# sensor-board.net
KiCad netlist of a schematic drawn in EAGLE
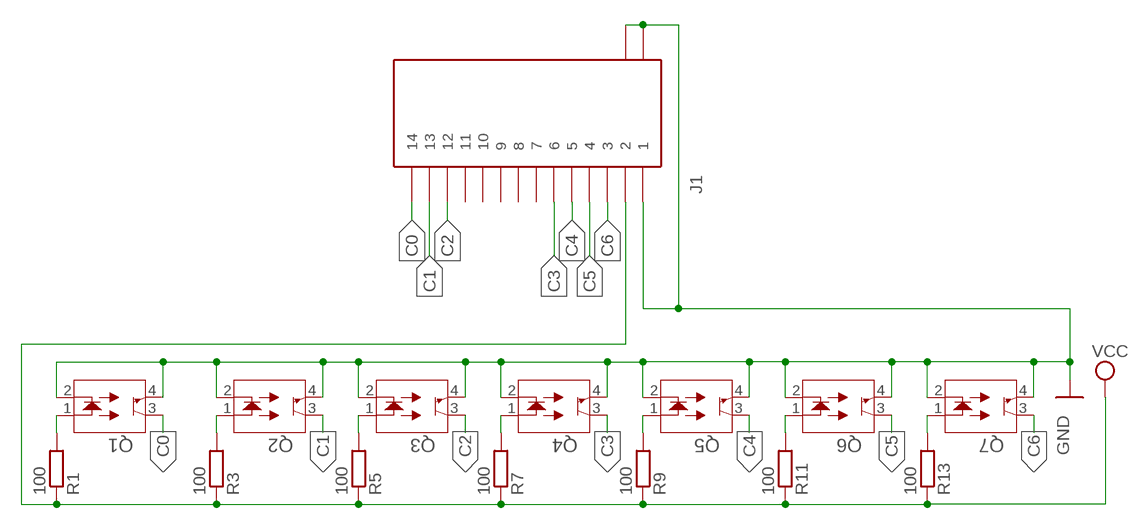
[diagram p0: schematic, sheet 1]

(export (version "E")
  (design (tool "Eeschema 10.0.6"))
  (components
    (comp (ref "J1")
      (value "686114148922")
      (footprint "eagle-import:686114148922")
      (fields (field (name "MOUSER_PART_NUMBER") "710-686114148922"))
      (libsource (lib "eagle-import") (part "686114148922"))
    )
    (comp (ref "Q1")
      (value "QRE1113")
      (footprint "eagle-import:DIP4_100AQ_ONS")
      (fields (field (name "COPYRIGHT") "Copyright (C) 2024 Ultra Librarian. All rights reserved."))
      (libsource (lib "eagle-import") (part "QRE1113"))
    )
    (comp (ref "Q2")
      (value "QRE1113")
      (footprint "eagle-import:DIP4_100AQ_ONS")
      (fields (field (name "COPYRIGHT") "Copyright (C) 2024 Ultra Librarian. All rights reserved."))
      (libsource (lib "eagle-import") (part "QRE1113"))
    )
    (comp (ref "Q3")
      (value "QRE1113")
      (footprint "eagle-import:DIP4_100AQ_ONS")
      (fields (field (name "COPYRIGHT") "Copyright (C) 2024 Ultra Librarian. All rights reserved."))
      (libsource (lib "eagle-import") (part "QRE1113"))
    )
    (comp (ref "Q4")
      (value "QRE1113")
      (footprint "eagle-import:DIP4_100AQ_ONS")
      (fields (field (name "COPYRIGHT") "Copyright (C) 2024 Ultra Librarian. All rights reserved."))
      (libsource (lib "eagle-import") (part "QRE1113"))
    )
    (comp (ref "Q5")
      (value "QRE1113")
      (footprint "eagle-import:DIP4_100AQ_ONS")
      (fields (field (name "COPYRIGHT") "Copyright (C) 2024 Ultra Librarian. All rights reserved."))
      (libsource (lib "eagle-import") (part "QRE1113"))
    )
    (comp (ref "Q6")
      (value "QRE1113")
      (footprint "eagle-import:DIP4_100AQ_ONS")
      (fields (field (name "COPYRIGHT") "Copyright (C) 2024 Ultra Librarian. All rights reserved."))
      (libsource (lib "eagle-import") (part "QRE1113"))
    )
    (comp (ref "Q7")
      (value "QRE1113")
      (footprint "eagle-import:DIP4_100AQ_ONS")
      (fields (field (name "COPYRIGHT") "Copyright (C) 2024 Ultra Librarian. All rights reserved."))
      (libsource (lib "eagle-import") (part "QRE1113"))
    )
    (comp (ref "R1")
      (value "100")
      (footprint "eagle-import:0207_10")
      (libsource (lib "eagle-import") (part "R-EU_0207/10"))
    )
    (comp (ref "R3")
      (value "100")
      (footprint "eagle-import:0207_10")
      (libsource (lib "eagle-import") (part "R-EU_0207/10"))
    )
    (comp (ref "R5")
      (value "100")
      (footprint "eagle-import:0207_10")
      (libsource (lib "eagle-import") (part "R-EU_0207/10"))
    )
    (comp (ref "R7")
      (value "100")
      (footprint "eagle-import:0207_10")
      (libsource (lib "eagle-import") (part "R-EU_0207/10"))
    )
    (comp (ref "R9")
      (value "100")
      (footprint "eagle-import:0207_10")
      (libsource (lib "eagle-import") (part "R-EU_0207/10"))
    )
    (comp (ref "R11")
      (value "100")
      (footprint "eagle-import:0207_10")
      (libsource (lib "eagle-import") (part "R-EU_0207/10"))
    )
    (comp (ref "R13")
      (value "100")
      (footprint "eagle-import:0207_10")
      (libsource (lib "eagle-import") (part "R-EU_0207/10"))
    )
  )
  (nets
    (net (code "1") (name "C0") (class "Default")
      (node (ref "J1") (pin "14") (pinfunction "14_14") (pintype "bidirectional"))
      (node (ref "Q1") (pin "3") (pinfunction "3_3") (pintype "passive"))
    )
    (net (code "2") (name "C1") (class "Default")
      (node (ref "J1") (pin "13") (pinfunction "13_13") (pintype "bidirectional"))
      (node (ref "Q2") (pin "3") (pinfunction "3_3") (pintype "passive"))
    )
    (net (code "3") (name "C2") (class "Default")
      (node (ref "J1") (pin "12") (pinfunction "12_12") (pintype "bidirectional"))
      (node (ref "Q3") (pin "3") (pinfunction "3_3") (pintype "passive"))
    )
    (net (code "4") (name "C3") (class "Default")
      (node (ref "J1") (pin "6") (pinfunction "6_6") (pintype "bidirectional"))
      (node (ref "Q4") (pin "3") (pinfunction "3_3") (pintype "passive"))
    )
    (net (code "5") (name "C4") (class "Default")
      (node (ref "J1") (pin "5") (pinfunction "5_5") (pintype "bidirectional"))
      (node (ref "Q5") (pin "3") (pinfunction "3_3") (pintype "passive"))
    )
    (net (code "6") (name "C5") (class "Default")
      (node (ref "J1") (pin "4") (pinfunction "4_4") (pintype "bidirectional"))
      (node (ref "Q6") (pin "3") (pinfunction "3_3") (pintype "passive"))
    )
    (net (code "7") (name "C6") (class "Default")
      (node (ref "J1") (pin "3") (pinfunction "3_3") (pintype "bidirectional"))
      (node (ref "Q7") (pin "3") (pinfunction "3_3") (pintype "passive"))
    )
    (net (code "8") (name "GND") (class "Default")
      (node (ref "J1") (pin "1") (pinfunction "1_1") (pintype "bidirectional"))
      (node (ref "J1") (pin "MP1") (pinfunction "MP1_MP1") (pintype "bidirectional"))
      (node (ref "J1") (pin "MP2") (pinfunction "MP2_MP2") (pintype "bidirectional"))
      (node (ref "Q1") (pin "2") (pinfunction "2_2") (pintype "passive"))
      (node (ref "Q1") (pin "4") (pinfunction "4_4") (pintype "passive"))
      (node (ref "Q2") (pin "2") (pinfunction "2_2") (pintype "passive"))
      (node (ref "Q2") (pin "4") (pinfunction "4_4") (pintype "passive"))
      (node (ref "Q3") (pin "2") (pinfunction "2_2") (pintype "passive"))
      (node (ref "Q3") (pin "4") (pinfunction "4_4") (pintype "passive"))
      (node (ref "Q4") (pin "2") (pinfunction "2_2") (pintype "passive"))
      (node (ref "Q4") (pin "4") (pinfunction "4_4") (pintype "passive"))
      (node (ref "Q5") (pin "2") (pinfunction "2_2") (pintype "passive"))
      (node (ref "Q5") (pin "4") (pinfunction "4_4") (pintype "passive"))
      (node (ref "Q6") (pin "2") (pinfunction "2_2") (pintype "passive"))
      (node (ref "Q6") (pin "4") (pinfunction "4_4") (pintype "passive"))
      (node (ref "Q7") (pin "2") (pinfunction "2_2") (pintype "passive"))
      (node (ref "Q7") (pin "4") (pinfunction "4_4") (pintype "passive"))
    )
    (net (code "9") (name "Net-(Q1-Pad1)") (class "Default")
      (node (ref "Q1") (pin "1") (pinfunction "1_1") (pintype "passive"))
      (node (ref "R1") (pin "2") (pinfunction "2_2") (pintype "passive"))
    )
    (net (code "10") (name "Net-(Q2-Pad1)") (class "Default")
      (node (ref "Q2") (pin "1") (pinfunction "1_1") (pintype "passive"))
      (node (ref "R3") (pin "2") (pinfunction "2_2") (pintype "passive"))
    )
    (net (code "11") (name "Net-(Q3-Pad1)") (class "Default")
      (node (ref "Q3") (pin "1") (pinfunction "1_1") (pintype "passive"))
      (node (ref "R5") (pin "2") (pinfunction "2_2") (pintype "passive"))
    )
    (net (code "12") (name "Net-(Q4-Pad1)") (class "Default")
      (node (ref "Q4") (pin "1") (pinfunction "1_1") (pintype "passive"))
      (node (ref "R7") (pin "2") (pinfunction "2_2") (pintype "passive"))
    )
    (net (code "13") (name "Net-(Q5-Pad1)") (class "Default")
      (node (ref "Q5") (pin "1") (pinfunction "1_1") (pintype "passive"))
      (node (ref "R9") (pin "2") (pinfunction "2_2") (pintype "passive"))
    )
    (net (code "14") (name "Net-(Q6-Pad1)") (class "Default")
      (node (ref "Q6") (pin "1") (pinfunction "1_1") (pintype "passive"))
      (node (ref "R11") (pin "2") (pinfunction "2_2") (pintype "passive"))
    )
    (net (code "15") (name "Net-(Q7-Pad1)") (class "Default")
      (node (ref "Q7") (pin "1") (pinfunction "1_1") (pintype "passive"))
      (node (ref "R13") (pin "2") (pinfunction "2_2") (pintype "passive"))
    )
    (net (code "16") (name "VCC") (class "Default")
      (node (ref "J1") (pin "2") (pinfunction "2_2") (pintype "bidirectional"))
      (node (ref "R1") (pin "1") (pinfunction "1_1") (pintype "passive"))
      (node (ref "R11") (pin "1") (pinfunction "1_1") (pintype "passive"))
      (node (ref "R13") (pin "1") (pinfunction "1_1") (pintype "passive"))
      (node (ref "R3") (pin "1") (pinfunction "1_1") (pintype "passive"))
      (node (ref "R5") (pin "1") (pinfunction "1_1") (pintype "passive"))
      (node (ref "R7") (pin "1") (pinfunction "1_1") (pintype "passive"))
      (node (ref "R9") (pin "1") (pinfunction "1_1") (pintype "passive"))
    )
    (net (code "17") (name "unconnected-(J1-Pad7)") (class "Default")
      (node (ref "J1") (pin "7") (pinfunction "7_7") (pintype "bidirectional"))
    )
    (net (code "18") (name "unconnected-(J1-Pad8)") (class "Default")
      (node (ref "J1") (pin "8") (pinfunction "8_8") (pintype "bidirectional"))
    )
    (net (code "19") (name "unconnected-(J1-Pad9)") (class "Default")
      (node (ref "J1") (pin "9") (pinfunction "9_9") (pintype "bidirectional"))
    )
    (net (code "20") (name "unconnected-(J1-Pad10)") (class "Default")
      (node (ref "J1") (pin "10") (pinfunction "10_10") (pintype "bidirectional"))
    )
    (net (code "21") (name "unconnected-(J1-Pad11)") (class "Default")
      (node (ref "J1") (pin "11") (pinfunction "11_11") (pintype "bidirectional"))
    )
  )
)
